# 8_-MODEM_MAIN.net
KiCad netlist of a schematic drawn in Altium Designer
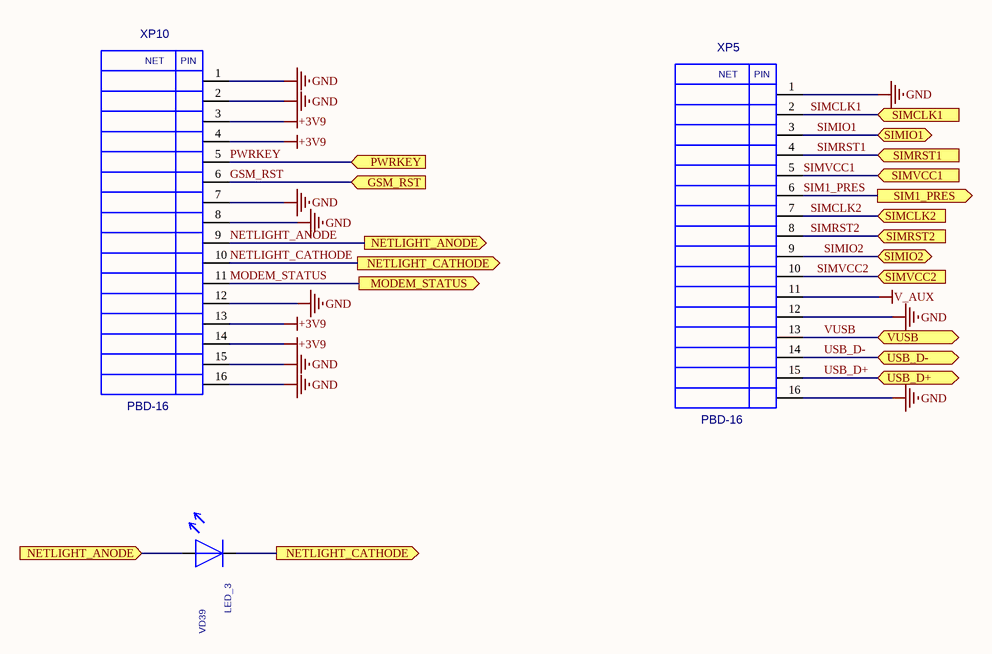
[diagram p0: [8]-MODEM_MAIN.SchDoc]

(export (version "E")
  (design (tool "Eeschema 10.0.6"))
  (components
    (comp (ref "VD39") (value "LED_3") (footprint "LED3") (libsource (lib "fizik_lib (1)") (part "LED_3")))
    (comp (ref "XP5") (value "PBD-16") (footprint "PBD16") (libsource (lib "fizik_lib") (part "PBD-16")))
    (comp (ref "XP10") (value "PBD-16") (footprint "PBD16") (libsource (lib "fizik_lib") (part "PBD-16")))
  )
  (nets
    (net (code "1") (name "+3V9") (class "Default")
      (node (ref "XP10") (pin "13") (pinfunction "13_13") (pintype "passive"))
      (node (ref "XP10") (pin "14") (pinfunction "14_14") (pintype "passive"))
      (node (ref "XP10") (pin "3") (pinfunction "3_3") (pintype "passive"))
      (node (ref "XP10") (pin "4") (pinfunction "4_4") (pintype "passive"))
    )
    (net (code "2") (name "/GSM_RST") (class "Default")
      (node (ref "XP10") (pin "6") (pinfunction "6_6") (pintype "passive"))
    )
    (net (code "3") (name "/MODEM_STATUS") (class "Default")
      (node (ref "XP10") (pin "11") (pinfunction "11_11") (pintype "passive"))
    )
    (net (code "4") (name "/NETLIGHT_ANODE") (class "Default")
      (node (ref "VD39") (pin "2") (pintype "passive"))
      (node (ref "XP10") (pin "9") (pinfunction "9_9") (pintype "passive"))
    )
    (net (code "5") (name "/NETLIGHT_CATHODE") (class "Default")
      (node (ref "VD39") (pin "1") (pintype "passive"))
      (node (ref "XP10") (pin "10") (pinfunction "10_10") (pintype "passive"))
    )
    (net (code "6") (name "/PWRKEY") (class "Default")
      (node (ref "XP10") (pin "5") (pinfunction "5_5") (pintype "passive"))
    )
    (net (code "7") (name "/SIM1_PRES") (class "Default")
      (node (ref "XP5") (pin "6") (pinfunction "6_6") (pintype "passive"))
    )
    (net (code "8") (name "/SIMCLK1") (class "Default")
      (node (ref "XP5") (pin "2") (pinfunction "2_2") (pintype "passive"))
    )
    (net (code "9") (name "/SIMCLK2") (class "Default")
      (node (ref "XP5") (pin "7") (pinfunction "7_7") (pintype "passive"))
    )
    (net (code "10") (name "/SIMIO1") (class "Default")
      (node (ref "XP5") (pin "3") (pinfunction "3_3") (pintype "passive"))
    )
    (net (code "11") (name "/SIMIO2") (class "Default")
      (node (ref "XP5") (pin "9") (pinfunction "9_9") (pintype "passive"))
    )
    (net (code "12") (name "/SIMRST1") (class "Default")
      (node (ref "XP5") (pin "4") (pinfunction "4_4") (pintype "passive"))
    )
    (net (code "13") (name "/SIMRST2") (class "Default")
      (node (ref "XP5") (pin "8") (pinfunction "8_8") (pintype "passive"))
    )
    (net (code "14") (name "/SIMVCC1") (class "Default")
      (node (ref "XP5") (pin "5") (pinfunction "5_5") (pintype "passive"))
    )
    (net (code "15") (name "/SIMVCC2") (class "Default")
      (node (ref "XP5") (pin "10") (pinfunction "10_10") (pintype "passive"))
    )
    (net (code "16") (name "/USB_D+") (class "Default")
      (node (ref "XP5") (pin "15") (pinfunction "15_15") (pintype "passive"))
    )
    (net (code "17") (name "/USB_D-") (class "Default")
      (node (ref "XP5") (pin "14") (pinfunction "14_14") (pintype "passive"))
    )
    (net (code "18") (name "/VUSB") (class "Default")
      (node (ref "XP5") (pin "13") (pinfunction "13_13") (pintype "passive"))
    )
    (net (code "19") (name "GND") (class "Default")
      (node (ref "XP10") (pin "1") (pinfunction "1_1") (pintype "passive"))
      (node (ref "XP10") (pin "12") (pinfunction "12_12") (pintype "passive"))
      (node (ref "XP10") (pin "15") (pinfunction "15_15") (pintype "passive"))
      (node (ref "XP10") (pin "16") (pinfunction "16_16") (pintype "passive"))
      (node (ref "XP10") (pin "2") (pinfunction "2_2") (pintype "passive"))
      (node (ref "XP10") (pin "7") (pinfunction "7_7") (pintype "passive"))
      (node (ref "XP10") (pin "8") (pinfunction "8_8") (pintype "passive"))
      (node (ref "XP5") (pin "1") (pinfunction "1_1") (pintype "passive"))
      (node (ref "XP5") (pin "12") (pinfunction "12_12") (pintype "passive"))
      (node (ref "XP5") (pin "16") (pinfunction "16_16") (pintype "passive"))
    )
    (net (code "20") (name "V_AUX") (class "Default")
      (node (ref "XP5") (pin "11") (pinfunction "11_11") (pintype "passive"))
    )
  )
)
